# 0-30bfp.net
KiCad netlist of a schematic drawn in EAGLE
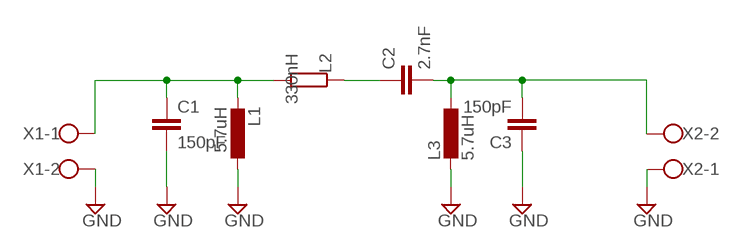
[diagram p0: schematic, sheet 1]

(export (version "E")
  (design (tool "Eeschema 10.0.6"))
  (components
    (comp (ref "C1")
      (value "150pF")
      (footprint "eagle-import:C1206K")
      (libsource (lib "eagle-import") (part "C-EUC1206K"))
    )
    (comp (ref "C2")
      (value "2.7nF")
      (footprint "eagle-import:C1206K")
      (libsource (lib "eagle-import") (part "C-EUC1206K"))
    )
    (comp (ref "C3")
      (value "150pF")
      (footprint "eagle-import:C1206K")
      (libsource (lib "eagle-import") (part "C-EUC1206K"))
    )
    (comp (ref "L1")
      (value "5.7uH")
      (footprint "eagle-import:0207_7")
      (libsource (lib "eagle-import") (part "L-EU0207/7"))
    )
    (comp (ref "L2")
      (value "330nH")
      (footprint "eagle-import:R1206")
      (libsource (lib "eagle-import") (part "R-EU_R1206"))
    )
    (comp (ref "L3")
      (value "5.7uH")
      (footprint "eagle-import:0207_7")
      (libsource (lib "eagle-import") (part "L-EU0207/7"))
    )
    (comp (ref "X1")
      (value "W237-102")
      (footprint "eagle-import:W237-102")
      (fields (field (name "MPN") "237-102"))
      (libsource (lib "eagle-import") (part "W237-102"))
    )
    (comp (ref "X2")
      (value "W237-102")
      (footprint "eagle-import:W237-102")
      (fields (field (name "MPN") "237-102"))
      (libsource (lib "eagle-import") (part "W237-102"))
    )
  )
  (nets
    (net (code "1") (name "GND") (class "Default")
      (node (ref "C1") (pin "2") (pinfunction "2_2") (pintype "passive"))
      (node (ref "C3") (pin "1") (pinfunction "1_1") (pintype "passive"))
      (node (ref "L1") (pin "1") (pinfunction "1_1") (pintype "passive"))
      (node (ref "L3") (pin "2") (pinfunction "2_2") (pintype "passive"))
      (node (ref "X1") (pin "2") (pinfunction "KL_2") (pintype "passive"))
      (node (ref "X2") (pin "1") (pinfunction "KL_1") (pintype "passive"))
    )
    (net (code "2") (name "Net-(C2-Pad1)") (class "Default")
      (node (ref "C2") (pin "1") (pinfunction "1_1") (pintype "passive"))
      (node (ref "L2") (pin "1") (pinfunction "1_1") (pintype "passive"))
    )
    (net (code "3") (name "Net-(X1A-KL)") (class "Default")
      (node (ref "C1") (pin "1") (pinfunction "1_1") (pintype "passive"))
      (node (ref "L1") (pin "2") (pinfunction "2_2") (pintype "passive"))
      (node (ref "L2") (pin "2") (pinfunction "2_2") (pintype "passive"))
      (node (ref "X1") (pin "1") (pinfunction "KL_1") (pintype "passive"))
    )
    (net (code "4") (name "Net-(X2B-KL)") (class "Default")
      (node (ref "C2") (pin "2") (pinfunction "2_2") (pintype "passive"))
      (node (ref "C3") (pin "2") (pinfunction "2_2") (pintype "passive"))
      (node (ref "L3") (pin "1") (pinfunction "1_1") (pintype "passive"))
      (node (ref "X2") (pin "2") (pinfunction "KL_2") (pintype "passive"))
    )
  )
)
